# IotaWatt3_2.net
KiCad netlist of a schematic drawn in EAGLE
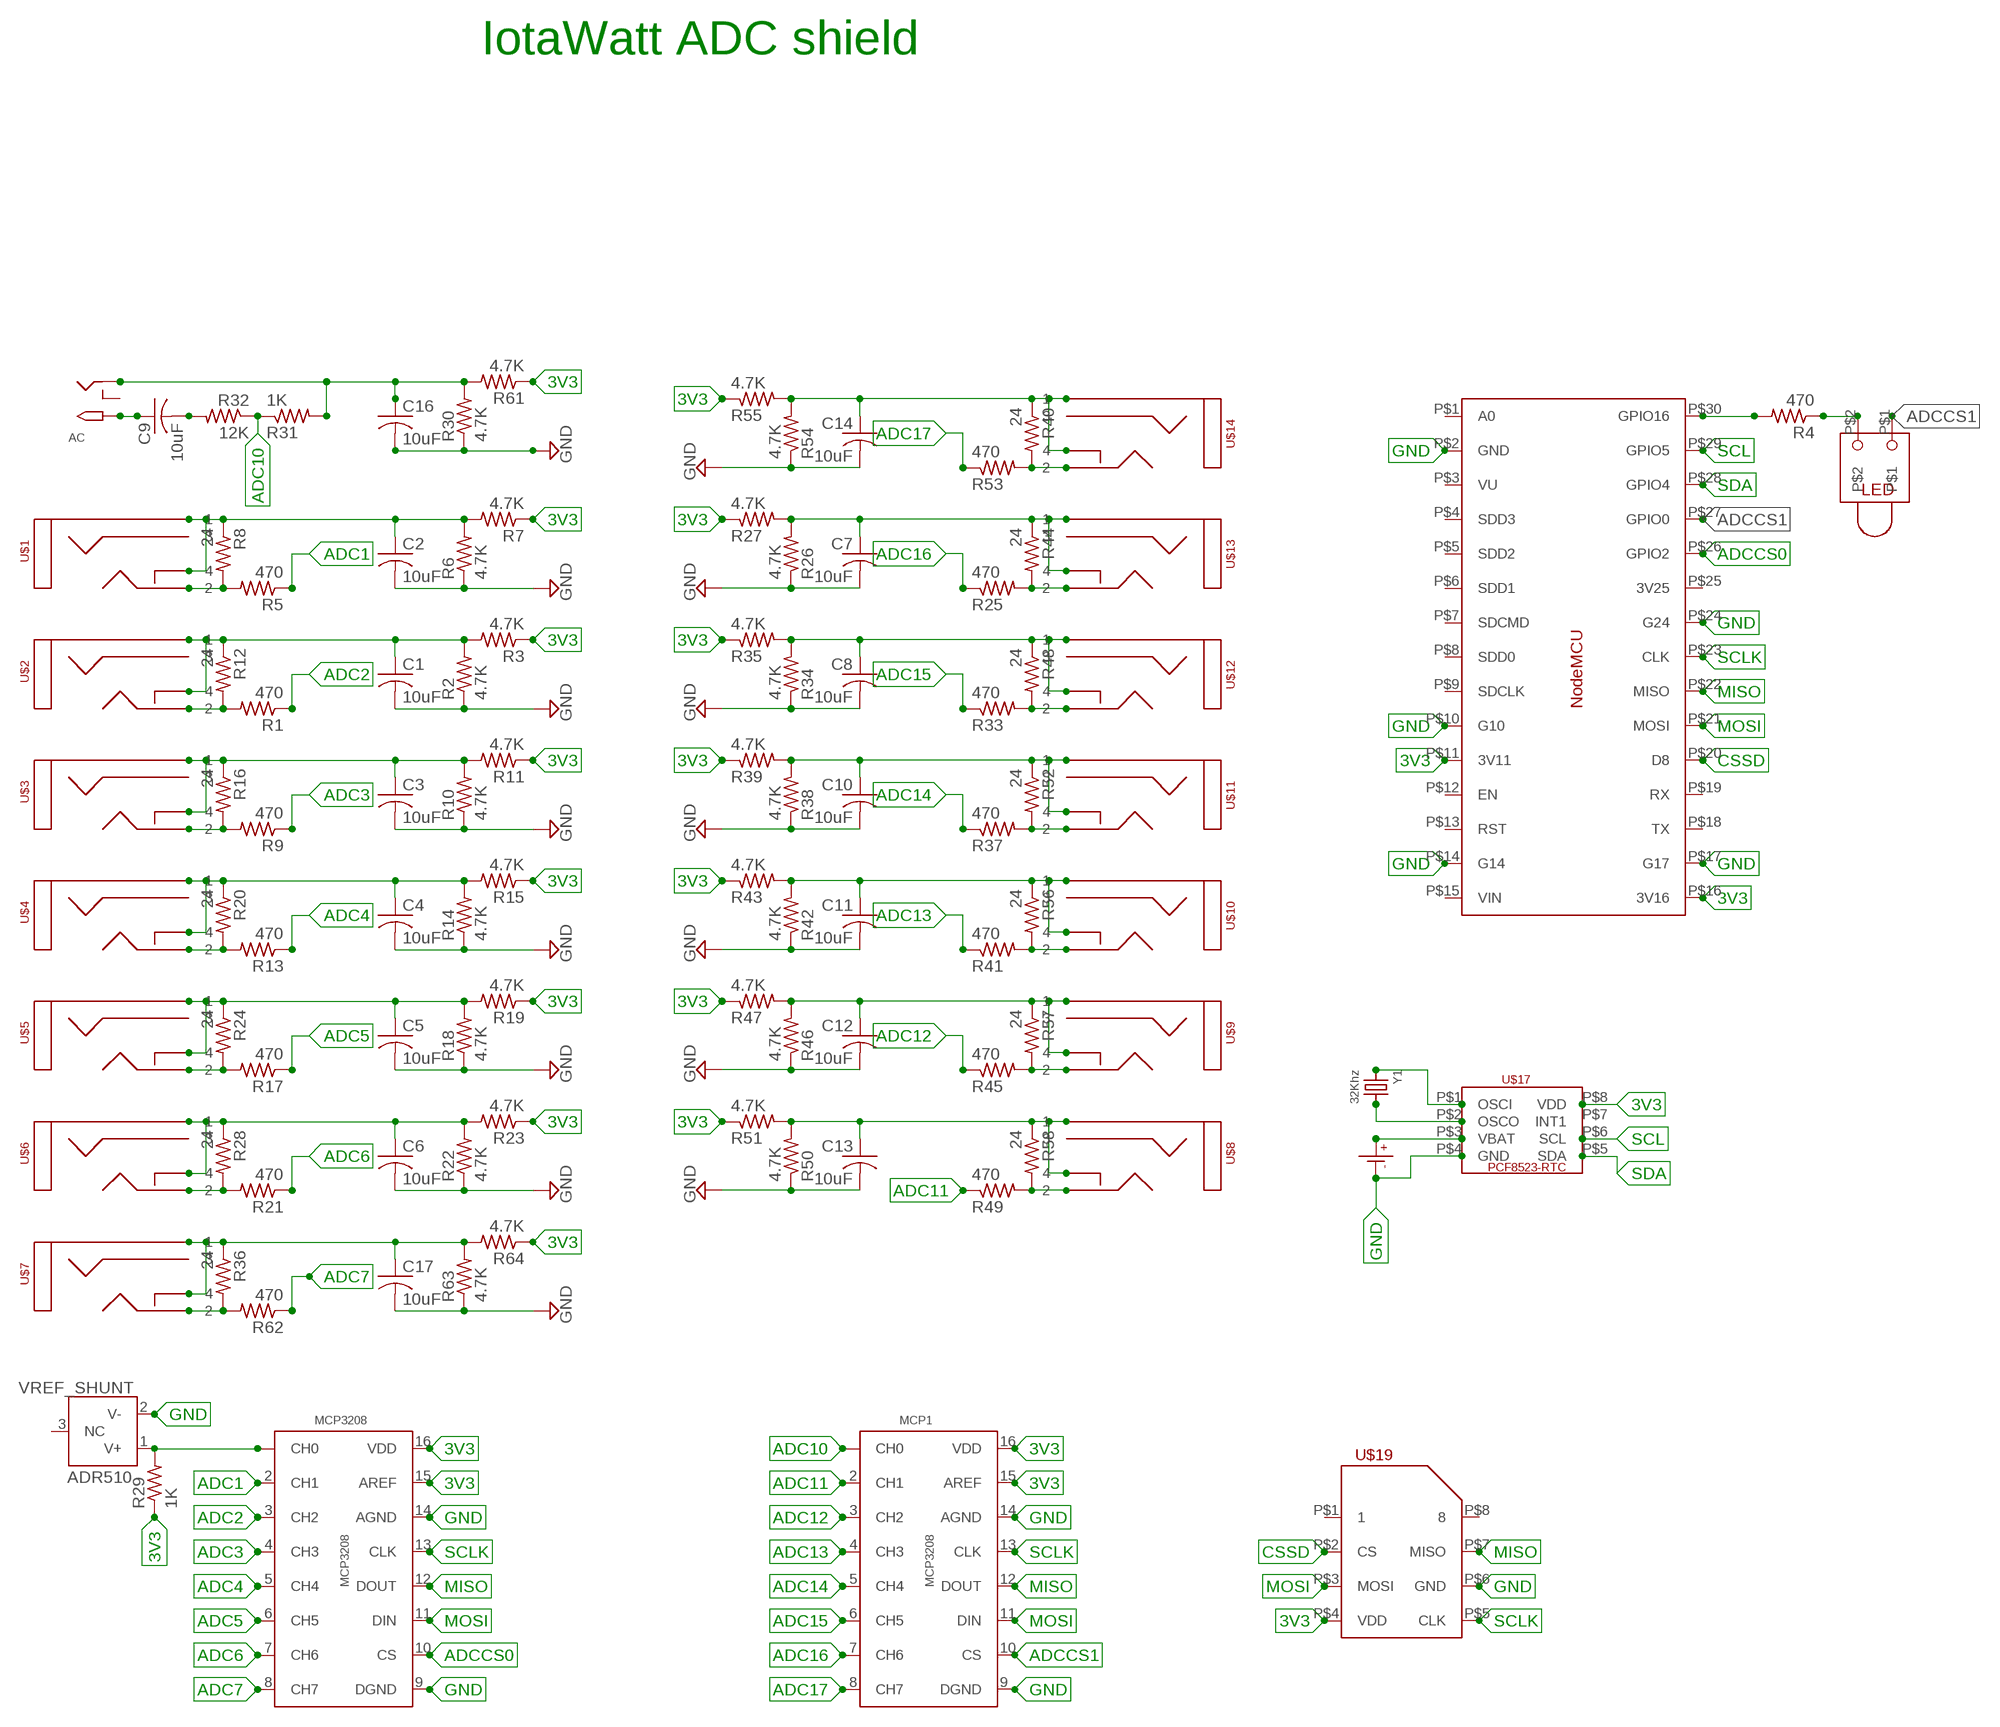
[diagram p0: schematic, sheet 1]

(export (version "E")
  (design (tool "Eeschema 10.0.6"))
  (components
    (comp (ref "AC")
      (value "2.1MMJACKSMT")
      (footprint "eagle-import:DCJACK_2MM_SMT")
      (libsource (lib "eagle-import") (part "2.1MMJACKSMT"))
    )
    (comp (ref "ADR510")
      (value "VREF_SHUNT")
      (footprint "eagle-import:SOT23_3")
      (libsource (lib "eagle-import") (part "VREF_SHUNT"))
    )
    (comp (ref "C1")
      (value "10uF")
      (footprint "eagle-import:C0805")
      (libsource (lib "eagle-import") (part "C-USC0805"))
    )
    (comp (ref "C2")
      (value "10uF")
      (footprint "eagle-import:C0805")
      (libsource (lib "eagle-import") (part "C-USC0805"))
    )
    (comp (ref "C3")
      (value "10uF")
      (footprint "eagle-import:C0805")
      (libsource (lib "eagle-import") (part "C-USC0805"))
    )
    (comp (ref "C4")
      (value "10uF")
      (footprint "eagle-import:C0805")
      (libsource (lib "eagle-import") (part "C-USC0805"))
    )
    (comp (ref "C5")
      (value "10uF")
      (footprint "eagle-import:C0805")
      (libsource (lib "eagle-import") (part "C-USC0805"))
    )
    (comp (ref "C6")
      (value "10uF")
      (footprint "eagle-import:C0805")
      (libsource (lib "eagle-import") (part "C-USC0805"))
    )
    (comp (ref "C7")
      (value "10uF")
      (footprint "eagle-import:C0805")
      (libsource (lib "eagle-import") (part "C-USC0805"))
    )
    (comp (ref "C8")
      (value "10uF")
      (footprint "eagle-import:C0805")
      (libsource (lib "eagle-import") (part "C-USC0805"))
    )
    (comp (ref "C9")
      (value "10uF")
      (footprint "eagle-import:C0805")
      (libsource (lib "eagle-import") (part "C-USC0805"))
    )
    (comp (ref "C10")
      (value "10uF")
      (footprint "eagle-import:C0805")
      (libsource (lib "eagle-import") (part "C-USC0805"))
    )
    (comp (ref "C11")
      (value "10uF")
      (footprint "eagle-import:C0805")
      (libsource (lib "eagle-import") (part "C-USC0805"))
    )
    (comp (ref "C12")
      (value "10uF")
      (footprint "eagle-import:C0805")
      (libsource (lib "eagle-import") (part "C-USC0805"))
    )
    (comp (ref "C13")
      (value "10uF")
      (footprint "eagle-import:C0805")
      (libsource (lib "eagle-import") (part "C-USC0805"))
    )
    (comp (ref "C14")
      (value "10uF")
      (footprint "eagle-import:C0805")
      (libsource (lib "eagle-import") (part "C-USC0805"))
    )
    (comp (ref "C16")
      (value "10uF")
      (footprint "eagle-import:C0805")
      (libsource (lib "eagle-import") (part "C-USC0805"))
    )
    (comp (ref "C17")
      (value "10uF")
      (footprint "eagle-import:C0805")
      (libsource (lib "eagle-import") (part "C-USC0805"))
    )
    (comp (ref "MCP1")
      (value "MCP3208")
      (footprint "eagle-import:SOIC_16")
      (libsource (lib "eagle-import") (part "MCP3208"))
    )
    (comp (ref "MCP3208")
      (value "MCP3208")
      (footprint "eagle-import:SOIC_16")
      (libsource (lib "eagle-import") (part "MCP3208"))
    )
    (comp (ref "R1")
      (value "470")
      (footprint "eagle-import:R0805")
      (libsource (lib "eagle-import") (part "R-US_R0805"))
    )
    (comp (ref "R2")
      (value "4.7K")
      (footprint "eagle-import:R0805")
      (libsource (lib "eagle-import") (part "R-US_R0805"))
    )
    (comp (ref "R3")
      (value "4.7K")
      (footprint "eagle-import:R0805")
      (libsource (lib "eagle-import") (part "R-US_R0805"))
    )
    (comp (ref "R4")
      (value "470")
      (footprint "eagle-import:R0805")
      (libsource (lib "eagle-import") (part "R-US_R0805"))
    )
    (comp (ref "R5")
      (value "470")
      (footprint "eagle-import:R0805")
      (libsource (lib "eagle-import") (part "R-US_R0805"))
    )
    (comp (ref "R6")
      (value "4.7K")
      (footprint "eagle-import:R0805")
      (libsource (lib "eagle-import") (part "R-US_R0805"))
    )
    (comp (ref "R7")
      (value "4.7K")
      (footprint "eagle-import:R0805")
      (libsource (lib "eagle-import") (part "R-US_R0805"))
    )
    (comp (ref "R8")
      (value "24")
      (footprint "eagle-import:R0805")
      (libsource (lib "eagle-import") (part "R-US_R0805"))
    )
    (comp (ref "R9")
      (value "470")
      (footprint "eagle-import:R0805")
      (libsource (lib "eagle-import") (part "R-US_R0805"))
    )
    (comp (ref "R10")
      (value "4.7K")
      (footprint "eagle-import:R0805")
      (libsource (lib "eagle-import") (part "R-US_R0805"))
    )
    (comp (ref "R11")
      (value "4.7K")
      (footprint "eagle-import:R0805")
      (libsource (lib "eagle-import") (part "R-US_R0805"))
    )
    (comp (ref "R12")
      (value "24")
      (footprint "eagle-import:R0805")
      (libsource (lib "eagle-import") (part "R-US_R0805"))
    )
    (comp (ref "R13")
      (value "470")
      (footprint "eagle-import:R0805")
      (libsource (lib "eagle-import") (part "R-US_R0805"))
    )
    (comp (ref "R14")
      (value "4.7K")
      (footprint "eagle-import:R0805")
      (libsource (lib "eagle-import") (part "R-US_R0805"))
    )
    (comp (ref "R15")
      (value "4.7K")
      (footprint "eagle-import:R0805")
      (libsource (lib "eagle-import") (part "R-US_R0805"))
    )
    (comp (ref "R16")
      (value "24")
      (footprint "eagle-import:R0805")
      (libsource (lib "eagle-import") (part "R-US_R0805"))
    )
    (comp (ref "R17")
      (value "470")
      (footprint "eagle-import:R0805")
      (libsource (lib "eagle-import") (part "R-US_R0805"))
    )
    (comp (ref "R18")
      (value "4.7K")
      (footprint "eagle-import:R0805")
      (libsource (lib "eagle-import") (part "R-US_R0805"))
    )
    (comp (ref "R19")
      (value "4.7K")
      (footprint "eagle-import:R0805")
      (libsource (lib "eagle-import") (part "R-US_R0805"))
    )
    (comp (ref "R20")
      (value "24")
      (footprint "eagle-import:R0805")
      (libsource (lib "eagle-import") (part "R-US_R0805"))
    )
    (comp (ref "R21")
      (value "470")
      (footprint "eagle-import:R0805")
      (libsource (lib "eagle-import") (part "R-US_R0805"))
    )
    (comp (ref "R22")
      (value "4.7K")
      (footprint "eagle-import:R0805")
      (libsource (lib "eagle-import") (part "R-US_R0805"))
    )
    (comp (ref "R23")
      (value "4.7K")
      (footprint "eagle-import:R0805")
      (libsource (lib "eagle-import") (part "R-US_R0805"))
    )
    (comp (ref "R24")
      (value "24")
      (footprint "eagle-import:R0805")
      (libsource (lib "eagle-import") (part "R-US_R0805"))
    )
    (comp (ref "R25")
      (value "470")
      (footprint "eagle-import:R0805")
      (libsource (lib "eagle-import") (part "R-US_R0805"))
    )
    (comp (ref "R26")
      (value "4.7K")
      (footprint "eagle-import:R0805")
      (libsource (lib "eagle-import") (part "R-US_R0805"))
    )
    (comp (ref "R27")
      (value "4.7K")
      (footprint "eagle-import:R0805")
      (libsource (lib "eagle-import") (part "R-US_R0805"))
    )
    (comp (ref "R28")
      (value "24")
      (footprint "eagle-import:R0805")
      (libsource (lib "eagle-import") (part "R-US_R0805"))
    )
    (comp (ref "R29")
      (value "1K")
      (footprint "eagle-import:R0805")
      (libsource (lib "eagle-import") (part "R-US_R0805"))
    )
    (comp (ref "R30")
      (value "4.7K")
      (footprint "eagle-import:R0805")
      (libsource (lib "eagle-import") (part "R-US_R0805"))
    )
    (comp (ref "R31")
      (value "1K")
      (footprint "eagle-import:R0805")
      (libsource (lib "eagle-import") (part "R-US_R0805"))
    )
    (comp (ref "R32")
      (value "12K")
      (footprint "eagle-import:R0805")
      (libsource (lib "eagle-import") (part "R-US_R0805"))
    )
    (comp (ref "R33")
      (value "470")
      (footprint "eagle-import:R0805")
      (libsource (lib "eagle-import") (part "R-US_R0805"))
    )
    (comp (ref "R34")
      (value "4.7K")
      (footprint "eagle-import:R0805")
      (libsource (lib "eagle-import") (part "R-US_R0805"))
    )
    (comp (ref "R35")
      (value "4.7K")
      (footprint "eagle-import:R0805")
      (libsource (lib "eagle-import") (part "R-US_R0805"))
    )
    (comp (ref "R36")
      (value "24")
      (footprint "eagle-import:R0805")
      (libsource (lib "eagle-import") (part "R-US_R0805"))
    )
    (comp (ref "R37")
      (value "470")
      (footprint "eagle-import:R0805")
      (libsource (lib "eagle-import") (part "R-US_R0805"))
    )
    (comp (ref "R38")
      (value "4.7K")
      (footprint "eagle-import:R0805")
      (libsource (lib "eagle-import") (part "R-US_R0805"))
    )
    (comp (ref "R39")
      (value "4.7K")
      (footprint "eagle-import:R0805")
      (libsource (lib "eagle-import") (part "R-US_R0805"))
    )
    (comp (ref "R40")
      (value "24")
      (footprint "eagle-import:R0805")
      (libsource (lib "eagle-import") (part "R-US_R0805"))
    )
    (comp (ref "R41")
      (value "470")
      (footprint "eagle-import:R0805")
      (libsource (lib "eagle-import") (part "R-US_R0805"))
    )
    (comp (ref "R42")
      (value "4.7K")
      (footprint "eagle-import:R0805")
      (libsource (lib "eagle-import") (part "R-US_R0805"))
    )
    (comp (ref "R43")
      (value "4.7K")
      (footprint "eagle-import:R0805")
      (libsource (lib "eagle-import") (part "R-US_R0805"))
    )
    (comp (ref "R44")
      (value "24")
      (footprint "eagle-import:R0805")
      (libsource (lib "eagle-import") (part "R-US_R0805"))
    )
    (comp (ref "R45")
      (value "470")
      (footprint "eagle-import:R0805")
      (libsource (lib "eagle-import") (part "R-US_R0805"))
    )
    (comp (ref "R46")
      (value "4.7K")
      (footprint "eagle-import:R0805")
      (libsource (lib "eagle-import") (part "R-US_R0805"))
    )
    (comp (ref "R47")
      (value "4.7K")
      (footprint "eagle-import:R0805")
      (libsource (lib "eagle-import") (part "R-US_R0805"))
    )
    (comp (ref "R48")
      (value "24")
      (footprint "eagle-import:R0805")
      (libsource (lib "eagle-import") (part "R-US_R0805"))
    )
    (comp (ref "R49")
      (value "470")
      (footprint "eagle-import:R0805")
      (libsource (lib "eagle-import") (part "R-US_R0805"))
    )
    (comp (ref "R50")
      (value "4.7K")
      (footprint "eagle-import:R0805")
      (libsource (lib "eagle-import") (part "R-US_R0805"))
    )
    (comp (ref "R51")
      (value "4.7K")
      (footprint "eagle-import:R0805")
      (libsource (lib "eagle-import") (part "R-US_R0805"))
    )
    (comp (ref "R52")
      (value "24")
      (footprint "eagle-import:R0805")
      (libsource (lib "eagle-import") (part "R-US_R0805"))
    )
    (comp (ref "R53")
      (value "470")
      (footprint "eagle-import:R0805")
      (libsource (lib "eagle-import") (part "R-US_R0805"))
    )
    (comp (ref "R54")
      (value "4.7K")
      (footprint "eagle-import:R0805")
      (libsource (lib "eagle-import") (part "R-US_R0805"))
    )
    (comp (ref "R55")
      (value "4.7K")
      (footprint "eagle-import:R0805")
      (libsource (lib "eagle-import") (part "R-US_R0805"))
    )
    (comp (ref "R56")
      (value "24")
      (footprint "eagle-import:R0805")
      (libsource (lib "eagle-import") (part "R-US_R0805"))
    )
    (comp (ref "R57")
      (value "24")
      (footprint "eagle-import:R0805")
      (libsource (lib "eagle-import") (part "R-US_R0805"))
    )
    (comp (ref "R58")
      (value "24")
      (footprint "eagle-import:R0805")
      (libsource (lib "eagle-import") (part "R-US_R0805"))
    )
    (comp (ref "R61")
      (value "4.7K")
      (footprint "eagle-import:R0805")
      (libsource (lib "eagle-import") (part "R-US_R0805"))
    )
    (comp (ref "R62")
      (value "470")
      (footprint "eagle-import:R0805")
      (libsource (lib "eagle-import") (part "R-US_R0805"))
    )
    (comp (ref "R63")
      (value "4.7K")
      (footprint "eagle-import:R0805")
      (libsource (lib "eagle-import") (part "R-US_R0805"))
    )
    (comp (ref "R64")
      (value "4.7K")
      (footprint "eagle-import:R0805")
      (libsource (lib "eagle-import") (part "R-US_R0805"))
    )
    (comp (ref "U$1")
      (value "STEREO_SMD")
      (footprint "eagle-import:STEREO_SMT")
      (libsource (lib "eagle-import") (part "STEREO_SMD"))
    )
    (comp (ref "U$2")
      (value "STEREO_SMD")
      (footprint "eagle-import:STEREO_SMT")
      (libsource (lib "eagle-import") (part "STEREO_SMD"))
    )
    (comp (ref "U$3")
      (value "STEREO_SMD")
      (footprint "eagle-import:STEREO_SMT")
      (libsource (lib "eagle-import") (part "STEREO_SMD"))
    )
    (comp (ref "U$4")
      (value "STEREO_SMD")
      (footprint "eagle-import:STEREO_SMT")
      (libsource (lib "eagle-import") (part "STEREO_SMD"))
    )
    (comp (ref "U$5")
      (value "STEREO_SMD")
      (footprint "eagle-import:STEREO_SMT")
      (libsource (lib "eagle-import") (part "STEREO_SMD"))
    )
    (comp (ref "U$6")
      (value "STEREO_SMD")
      (footprint "eagle-import:STEREO_SMT")
      (libsource (lib "eagle-import") (part "STEREO_SMD"))
    )
    (comp (ref "U$7")
      (value "STEREO_SMD")
      (footprint "eagle-import:STEREO_SMT")
      (libsource (lib "eagle-import") (part "STEREO_SMD"))
    )
    (comp (ref "U$8")
      (value "STEREO_SMD")
      (footprint "eagle-import:STEREO_SMT")
      (libsource (lib "eagle-import") (part "STEREO_SMD"))
    )
    (comp (ref "U$9")
      (value "STEREO_SMD")
      (footprint "eagle-import:STEREO_SMT")
      (libsource (lib "eagle-import") (part "STEREO_SMD"))
    )
    (comp (ref "U$10")
      (value "STEREO_SMD")
      (footprint "eagle-import:STEREO_SMT")
      (libsource (lib "eagle-import") (part "STEREO_SMD"))
    )
    (comp (ref "U$11")
      (value "STEREO_SMD")
      (footprint "eagle-import:STEREO_SMT")
      (libsource (lib "eagle-import") (part "STEREO_SMD"))
    )
    (comp (ref "U$12")
      (value "STEREO_SMD")
      (footprint "eagle-import:STEREO_SMT")
      (libsource (lib "eagle-import") (part "STEREO_SMD"))
    )
    (comp (ref "U$13")
      (value "STEREO_SMD")
      (footprint "eagle-import:STEREO_SMT")
      (libsource (lib "eagle-import") (part "STEREO_SMD"))
    )
    (comp (ref "U$14")
      (value "STEREO_SMD")
      (footprint "eagle-import:STEREO_SMT")
      (libsource (lib "eagle-import") (part "STEREO_SMD"))
    )
    (comp (ref "U$15")
      (value "LED_RT_TRH")
      (footprint "eagle-import:LED_TH_RT")
      (libsource (lib "eagle-import") (part "LED_RT_TRH"))
    )
    (comp (ref "U$16")
      (value "NODEMCU")
      (footprint "eagle-import:NODEMCU")
      (libsource (lib "eagle-import") (part "NODEMCU"))
    )
    (comp (ref "U$17")
      (value "PCF8523_RTC")
      (footprint "eagle-import:SOIC_8")
      (libsource (lib "eagle-import") (part "PCF8523_RTC"))
    )
    (comp (ref "U$18")
      (value "CR1220SMD")
      (footprint "eagle-import:CR1220SMD")
      (libsource (lib "eagle-import") (part "CR1220SMD"))
    )
    (comp (ref "U$19")
      (value "MICROSD_PUSH/PULL")
      (footprint "eagle-import:MICROSD")
      (libsource (lib "eagle-import") (part "MICROSD_PUSH/PULL"))
    )
    (comp (ref "Y1")
      (value "32Khz")
      (footprint "eagle-import:CRYSTAL_8X3.8")
      (libsource (lib "eagle-import") (part "CRYSTAL8X3.8SMT"))
    )
  )
  (nets
    (net (code "1") (name "3V3") (class "Default")
      (node (ref "MCP1") (pin "15") (pinfunction "AREF_15") (pintype "input"))
      (node (ref "MCP1") (pin "16") (pinfunction "VDD_16") (pintype "bidirectional"))
      (node (ref "MCP3208") (pin "15") (pinfunction "AREF_15") (pintype "input"))
      (node (ref "MCP3208") (pin "16") (pinfunction "VDD_16") (pintype "bidirectional"))
      (node (ref "R11") (pin "1") (pinfunction "1_1") (pintype "passive"))
      (node (ref "R15") (pin "1") (pinfunction "1_1") (pintype "passive"))
      (node (ref "R19") (pin "1") (pinfunction "1_1") (pintype "passive"))
      (node (ref "R23") (pin "1") (pinfunction "1_1") (pintype "passive"))
      (node (ref "R27") (pin "1") (pinfunction "1_1") (pintype "passive"))
      (node (ref "R29") (pin "1") (pinfunction "1_1") (pintype "passive"))
      (node (ref "R3") (pin "1") (pinfunction "1_1") (pintype "passive"))
      (node (ref "R35") (pin "1") (pinfunction "1_1") (pintype "passive"))
      (node (ref "R39") (pin "1") (pinfunction "1_1") (pintype "passive"))
      (node (ref "R43") (pin "1") (pinfunction "1_1") (pintype "passive"))
      (node (ref "R47") (pin "1") (pinfunction "1_1") (pintype "passive"))
      (node (ref "R51") (pin "1") (pinfunction "1_1") (pintype "passive"))
      (node (ref "R55") (pin "1") (pinfunction "1_1") (pintype "passive"))
      (node (ref "R61") (pin "1") (pinfunction "1_1") (pintype "passive"))
      (node (ref "R64") (pin "1") (pinfunction "1_1") (pintype "passive"))
      (node (ref "R7") (pin "1") (pinfunction "1_1") (pintype "passive"))
      (node (ref "U$16") (pin "P$11") (pinfunction "3V11_P$11") (pintype "bidirectional"))
      (node (ref "U$16") (pin "P$16") (pinfunction "3V16_P$16") (pintype "bidirectional"))
      (node (ref "U$17") (pin "P$8") (pinfunction "VDD_P$8") (pintype "bidirectional"))
      (node (ref "U$19") (pin "P$4") (pinfunction "VDD_P$4") (pintype "bidirectional"))
    )
    (net (code "2") (name "ADC1") (class "Default")
      (node (ref "MCP3208") (pin "2") (pinfunction "CH1_2") (pintype "input"))
      (node (ref "R5") (pin "1") (pinfunction "1_1") (pintype "passive"))
    )
    (net (code "3") (name "ADC2") (class "Default")
      (node (ref "MCP3208") (pin "3") (pinfunction "CH2_3") (pintype "input"))
      (node (ref "R1") (pin "1") (pinfunction "1_1") (pintype "passive"))
    )
    (net (code "4") (name "ADC3") (class "Default")
      (node (ref "MCP3208") (pin "4") (pinfunction "CH3_4") (pintype "input"))
      (node (ref "R9") (pin "1") (pinfunction "1_1") (pintype "passive"))
    )
    (net (code "5") (name "ADC4") (class "Default")
      (node (ref "MCP3208") (pin "5") (pinfunction "CH4_5") (pintype "bidirectional"))
      (node (ref "R13") (pin "1") (pinfunction "1_1") (pintype "passive"))
    )
    (net (code "6") (name "ADC5") (class "Default")
      (node (ref "MCP3208") (pin "6") (pinfunction "CH5_6") (pintype "bidirectional"))
      (node (ref "R17") (pin "1") (pinfunction "1_1") (pintype "passive"))
    )
    (net (code "7") (name "ADC6") (class "Default")
      (node (ref "MCP3208") (pin "7") (pinfunction "CH6_7") (pintype "input"))
      (node (ref "R21") (pin "1") (pinfunction "1_1") (pintype "passive"))
    )
    (net (code "8") (name "ADC7") (class "Default")
      (node (ref "MCP3208") (pin "8") (pinfunction "CH7_8") (pintype "bidirectional"))
      (node (ref "R62") (pin "1") (pinfunction "1_1") (pintype "passive"))
    )
    (net (code "9") (name "ADC10") (class "Default")
      (node (ref "MCP1") (pin "1") (pinfunction "CH0_1") (pintype "input"))
      (node (ref "R31") (pin "1") (pinfunction "1_1") (pintype "passive"))
      (node (ref "R32") (pin "1") (pinfunction "1_1") (pintype "passive"))
    )
    (net (code "10") (name "ADC11") (class "Default")
      (node (ref "MCP1") (pin "2") (pinfunction "CH1_2") (pintype "input"))
      (node (ref "R49") (pin "1") (pinfunction "1_1") (pintype "passive"))
    )
    (net (code "11") (name "ADC12") (class "Default")
      (node (ref "MCP1") (pin "3") (pinfunction "CH2_3") (pintype "input"))
      (node (ref "R45") (pin "1") (pinfunction "1_1") (pintype "passive"))
    )
    (net (code "12") (name "ADC13") (class "Default")
      (node (ref "MCP1") (pin "4") (pinfunction "CH3_4") (pintype "input"))
      (node (ref "R41") (pin "1") (pinfunction "1_1") (pintype "passive"))
    )
    (net (code "13") (name "ADC14") (class "Default")
      (node (ref "MCP1") (pin "5") (pinfunction "CH4_5") (pintype "bidirectional"))
      (node (ref "R37") (pin "1") (pinfunction "1_1") (pintype "passive"))
    )
    (net (code "14") (name "ADC15") (class "Default")
      (node (ref "MCP1") (pin "6") (pinfunction "CH5_6") (pintype "bidirectional"))
      (node (ref "R33") (pin "1") (pinfunction "1_1") (pintype "passive"))
    )
    (net (code "15") (name "ADC16") (class "Default")
      (node (ref "MCP1") (pin "7") (pinfunction "CH6_7") (pintype "input"))
      (node (ref "R25") (pin "1") (pinfunction "1_1") (pintype "passive"))
    )
    (net (code "16") (name "ADC17") (class "Default")
      (node (ref "MCP1") (pin "8") (pinfunction "CH7_8") (pintype "bidirectional"))
      (node (ref "R53") (pin "1") (pinfunction "1_1") (pintype "passive"))
    )
    (net (code "17") (name "ADCCS0") (class "Default")
      (node (ref "MCP3208") (pin "10") (pinfunction "CS_10") (pintype "input"))
      (node (ref "U$16") (pin "P$26") (pinfunction "GPIO2_P$26") (pintype "bidirectional"))
    )
    (net (code "18") (name "ADCCS1") (class "Default")
      (node (ref "MCP1") (pin "10") (pinfunction "CS_10") (pintype "input"))
      (node (ref "U$15") (pin "P$1") (pinfunction "P$1_P$1") (pintype "bidirectional"))
      (node (ref "U$16") (pin "P$27") (pinfunction "GPIO0_P$27") (pintype "bidirectional"))
    )
    (net (code "19") (name "CSSD") (class "Default")
      (node (ref "U$16") (pin "P$20") (pinfunction "D8_P$20") (pintype "bidirectional"))
      (node (ref "U$19") (pin "P$2") (pinfunction "CS_P$2") (pintype "bidirectional"))
    )
    (net (code "20") (name "GND") (class "Default")
      (node (ref "ADR510") (pin "2") (pinfunction "V-_2") (pintype "bidirectional"))
      (node (ref "C1") (pin "2") (pinfunction "2_2") (pintype "passive"))
      (node (ref "C10") (pin "2") (pinfunction "2_2") (pintype "passive"))
      (node (ref "C11") (pin "2") (pinfunction "2_2") (pintype "passive"))
      (node (ref "C12") (pin "2") (pinfunction "2_2") (pintype "passive"))
      (node (ref "C13") (pin "2") (pinfunction "2_2") (pintype "passive"))
      (node (ref "C14") (pin "2") (pinfunction "2_2") (pintype "passive"))
      (node (ref "C16") (pin "2") (pinfunction "2_2") (pintype "passive"))
      (node (ref "C17") (pin "2") (pinfunction "2_2") (pintype "passive"))
      (node (ref "C2") (pin "2") (pinfunction "2_2") (pintype "passive"))
      (node (ref "C3") (pin "2") (pinfunction "2_2") (pintype "passive"))
      (node (ref "C4") (pin "2") (pinfunction "2_2") (pintype "passive"))
      (node (ref "C5") (pin "2") (pinfunction "2_2") (pintype "passive"))
      (node (ref "C6") (pin "2") (pinfunction "2_2") (pintype "passive"))
      (node (ref "C7") (pin "2") (pinfunction "2_2") (pintype "passive"))
      (node (ref "C8") (pin "2") (pinfunction "2_2") (pintype "passive"))
      (node (ref "MCP1") (pin "14") (pinfunction "AGND_14") (pintype "input"))
      (node (ref "MCP1") (pin "9") (pinfunction "DGND_9") (pintype "bidirectional"))
      (node (ref "MCP3208") (pin "14") (pinfunction "AGND_14") (pintype "input"))
      (node (ref "MCP3208") (pin "9") (pinfunction "DGND_9") (pintype "bidirectional"))
      (node (ref "R10") (pin "1") (pinfunction "1_1") (pintype "passive"))
      (node (ref "R14") (pin "1") (pinfunction "1_1") (pintype "passive"))
      (node (ref "R18") (pin "1") (pinfunction "1_1") (pintype "passive"))
      (node (ref "R2") (pin "1") (pinfunction "1_1") (pintype "passive"))
      (node (ref "R22") (pin "1") (pinfunction "1_1") (pintype "passive"))
      (node (ref "R26") (pin "1") (pinfunction "1_1") (pintype "passive"))
      (node (ref "R30") (pin "1") (pinfunction "1_1") (pintype "passive"))
      (node (ref "R34") (pin "1") (pinfunction "1_1") (pintype "passive"))
      (node (ref "R38") (pin "1") (pinfunction "1_1") (pintype "passive"))
      (node (ref "R42") (pin "1") (pinfunction "1_1") (pintype "passive"))
      (node (ref "R46") (pin "1") (pinfunction "1_1") (pintype "passive"))
      (node (ref "R50") (pin "1") (pinfunction "1_1") (pintype "passive"))
      (node (ref "R54") (pin "1") (pinfunction "1_1") (pintype "passive"))
      (node (ref "R6") (pin "1") (pinfunction "1_1") (pintype "passive"))
      (node (ref "R63") (pin "1") (pinfunction "1_1") (pintype "passive"))
      (node (ref "U$16") (pin "P$10") (pinfunction "G10_P$10") (pintype "bidirectional"))
      (node (ref "U$16") (pin "P$14") (pinfunction "G14_P$14") (pintype "bidirectional"))
      (node (ref "U$16") (pin "P$17") (pinfunction "G17_P$17") (pintype "bidirectional"))
      (node (ref "U$16") (pin "P$2") (pinfunction "GND_P$2") (pintype "bidirectional"))
      (node (ref "U$16") (pin "P$24") (pinfunction "G24_P$24") (pintype "bidirectional"))
      (node (ref "U$17") (pin "P$4") (pinfunction "GND_P$4") (pintype "bidirectional"))
      (node (ref "U$18") (pin "P-") (pinfunction "P$-_P-") (pintype "bidirectional"))
      (node (ref "U$19") (pin "P$6") (pinfunction "GND_P$6") (pintype "bidirectional"))
    )
    (net (code "21") (name "MISO") (class "Default")
      (node (ref "MCP1") (pin "12") (pinfunction "DOUT_12") (pintype "bidirectional"))
      (node (ref "MCP3208") (pin "12") (pinfunction "DOUT_12") (pintype "bidirectional"))
      (node (ref "U$16") (pin "P$22") (pinfunction "MISO_P$22") (pintype "bidirectional"))
      (node (ref "U$19") (pin "P$7") (pinfunction "MISO_P$7") (pintype "bidirectional"))
    )
    (net (code "22") (name "MOSI") (class "Default")
      (node (ref "MCP1") (pin "11") (pinfunction "DIN_11") (pintype "input"))
      (node (ref "MCP3208") (pin "11") (pinfunction "DIN_11") (pintype "input"))
      (node (ref "U$16") (pin "P$21") (pinfunction "MOSI_P$21") (pintype "bidirectional"))
      (node (ref "U$19") (pin "P$3") (pinfunction "MOSI_P$3") (pintype "bidirectional"))
    )
    (net (code "23") (name "Net-(AC-RING)") (class "Default")
      (node (ref "AC") (pin "GND") (pinfunction "RING_GND") (pintype "bidirectional"))
      (node (ref "C16") (pin "1") (pinfunction "1_1") (pintype "passive"))
      (node (ref "R30") (pin "2") (pinfunction "2_2") (pintype "passive"))
      (node (ref "R31") (pin "2") (pinfunction "2_2") (pintype "passive"))
      (node (ref "R61") (pin "2") (pinfunction "2_2") (pintype "passive"))
    )
    (net (code "24") (name "Net-(AC-TIP)") (class "Default")
      (node (ref "AC") (pin "PWR2") (pinfunction "TIP_PWR2") (pintype "bidirectional"))
      (node (ref "C9") (pin "1") (pinfunction "1_1") (pintype "passive"))
    )
    (net (code "25") (name "Net-(ADR510-V+)") (class "Default")
      (node (ref "ADR510") (pin "1") (pinfunction "V+_1") (pintype "bidirectional"))
      (node (ref "MCP3208") (pin "1") (pinfunction "CH0_1") (pintype "input"))
      (node (ref "R29") (pin "2") (pinfunction "2_2") (pintype "passive"))
    )
    (net (code "26") (name "Net-(C9-Pad2)") (class "Default")
      (node (ref "C9") (pin "2") (pinfunction "2_2") (pintype "passive"))
      (node (ref "R32") (pin "2") (pinfunction "2_2") (pintype "passive"))
    )
    (net (code "27") (name "Net-(R4-Pad1)") (class "Default")
      (node (ref "R4") (pin "1") (pinfunction "1_1") (pintype "passive"))
      (node (ref "U$15") (pin "P$2") (pinfunction "P$2_P$2") (pintype "bidirectional"))
    )
    (net (code "28") (name "Net-(U$1-1)") (class "Default")
      (node (ref "C2") (pin "1") (pinfunction "1_1") (pintype "passive"))
      (node (ref "R6") (pin "2") (pinfunction "2_2") (pintype "passive"))
      (node (ref "R7") (pin "2") (pinfunction "2_2") (pintype "passive"))
      (node (ref "R8") (pin "1") (pinfunction "1_1") (pintype "passive"))
      (node (ref "U$1") (pin "P$1") (pinfunction "1_P$1") (pintype "bidirectional"))
      (node (ref "U$1") (pin "P$4") (pinfunction "4_P$4") (pintype "bidirectional"))
    )
    (net (code "29") (name "Net-(U$1-2)") (class "Default")
      (node (ref "R5") (pin "2") (pinfunction "2_2") (pintype "passive"))
      (node (ref "R8") (pin "2") (pinfunction "2_2") (pintype "passive"))
      (node (ref "U$1") (pin "P$2") (pinfunction "2_P$2") (pintype "bidirectional"))
    )
    (net (code "30") (name "Net-(U$2-1)") (class "Default")
      (node (ref "C1") (pin "1") (pinfunction "1_1") (pintype "passive"))
      (node (ref "R12") (pin "1") (pinfunction "1_1") (pintype "passive"))
      (node (ref "R2") (pin "2") (pinfunction "2_2") (pintype "passive"))
      (node (ref "R3") (pin "2") (pinfunction "2_2") (pintype "passive"))
      (node (ref "U$2") (pin "P$1") (pinfunction "1_P$1") (pintype "bidirectional"))
      (node (ref "U$2") (pin "P$4") (pinfunction "4_P$4") (pintype "bidirectional"))
    )
    (net (code "31") (name "Net-(U$2-2)") (class "Default")
      (node (ref "R1") (pin "2") (pinfunction "2_2") (pintype "passive"))
      (node (ref "R12") (pin "2") (pinfunction "2_2") (pintype "passive"))
      (node (ref "U$2") (pin "P$2") (pinfunction "2_P$2") (pintype "bidirectional"))
    )
    (net (code "32") (name "Net-(U$3-1)") (class "Default")
      (node (ref "C3") (pin "1") (pinfunction "1_1") (pintype "passive"))
      (node (ref "R10") (pin "2") (pinfunction "2_2") (pintype "passive"))
      (node (ref "R11") (pin "2") (pinfunction "2_2") (pintype "passive"))
      (node (ref "R16") (pin "1") (pinfunction "1_1") (pintype "passive"))
      (node (ref "U$3") (pin "P$1") (pinfunction "1_P$1") (pintype "bidirectional"))
      (node (ref "U$3") (pin "P$4") (pinfunction "4_P$4") (pintype "bidirectional"))
    )
    (net (code "33") (name "Net-(U$3-2)") (class "Default")
      (node (ref "R16") (pin "2") (pinfunction "2_2") (pintype "passive"))
      (node (ref "R9") (pin "2") (pinfunction "2_2") (pintype "passive"))
      (node (ref "U$3") (pin "P$2") (pinfunction "2_P$2") (pintype "bidirectional"))
    )
    (net (code "34") (name "Net-(U$4-1)") (class "Default")
      (node (ref "C4") (pin "1") (pinfunction "1_1") (pintype "passive"))
      (node (ref "R14") (pin "2") (pinfunction "2_2") (pintype "passive"))
      (node (ref "R15") (pin "2") (pinfunction "2_2") (pintype "passive"))
      (node (ref "R20") (pin "1") (pinfunction "1_1") (pintype "passive"))
      (node (ref "U$4") (pin "P$1") (pinfunction "1_P$1") (pintype "bidirectional"))
      (node (ref "U$4") (pin "P$4") (pinfunction "4_P$4") (pintype "bidirectional"))
    )
    (net (code "35") (name "Net-(U$4-2)") (class "Default")
      (node (ref "R13") (pin "2") (pinfunction "2_2") (pintype "passive"))
      (node (ref "R20") (pin "2") (pinfunction "2_2") (pintype "passive"))
      (node (ref "U$4") (pin "P$2") (pinfunction "2_P$2") (pintype "bidirectional"))
    )
    (net (code "36") (name "Net-(U$5-1)") (class "Default")
      (node (ref "C5") (pin "1") (pinfunction "1_1") (pintype "passive"))
      (node (ref "R18") (pin "2") (pinfunction "2_2") (pintype "passive"))
      (node (ref "R19") (pin "2") (pinfunction "2_2") (pintype "passive"))
      (node (ref "R24") (pin "1") (pinfunction "1_1") (pintype "passive"))
      (node (ref "U$5") (pin "P$1") (pinfunction "1_P$1") (pintype "bidirectional"))
      (node (ref "U$5") (pin "P$4") (pinfunction "4_P$4") (pintype "bidirectional"))
    )
    (net (code "37") (name "Net-(U$5-2)") (class "Default")
      (node (ref "R17") (pin "2") (pinfunction "2_2") (pintype "passive"))
      (node (ref "R24") (pin "2") (pinfunction "2_2") (pintype "passive"))
      (node (ref "U$5") (pin "P$2") (pinfunction "2_P$2") (pintype "bidirectional"))
    )
    (net (code "38") (name "Net-(U$6-1)") (class "Default")
      (node (ref "C6") (pin "1") (pinfunction "1_1") (pintype "passive"))
      (node (ref "R22") (pin "2") (pinfunction "2_2") (pintype "passive"))
      (node (ref "R23") (pin "2") (pinfunction "2_2") (pintype "passive"))
      (node (ref "R28") (pin "1") (pinfunction "1_1") (pintype "passive"))
      (node (ref "U$6") (pin "P$1") (pinfunction "1_P$1") (pintype "bidirectional"))
      (node (ref "U$6") (pin "P$4") (pinfunction "4_P$4") (pintype "bidirectional"))
    )
    (net (code "39") (name "Net-(U$6-2)") (class "Default")
      (node (ref "R21") (pin "2") (pinfunction "2_2") (pintype "passive"))
      (node (ref "R28") (pin "2") (pinfunction "2_2") (pintype "passive"))
      (node (ref "U$6") (pin "P$2") (pinfunction "2_P$2") (pintype "bidirectional"))
    )
    (net (code "40") (name "Net-(U$7-1)") (class "Default")
      (node (ref "C17") (pin "1") (pinfunction "1_1") (pintype "passive"))
      (node (ref "R36") (pin "1") (pinfunction "1_1") (pintype "passive"))
      (node (ref "R63") (pin "2") (pinfunction "2_2") (pintype "passive"))
      (node (ref "R64") (pin "2") (pinfunction "2_2") (pintype "passive"))
      (node (ref "U$7") (pin "P$1") (pinfunction "1_P$1") (pintype "bidirectional"))
      (node (ref "U$7") (pin "P$4") (pinfunction "4_P$4") (pintype "bidirectional"))
    )
    (net (code "41") (name "Net-(U$7-2)") (class "Default")
      (node (ref "R36") (pin "2") (pinfunction "2_2") (pintype "passive"))
      (node (ref "R62") (pin "2") (pinfunction "2_2") (pintype "passive"))
      (node (ref "U$7") (pin "P$2") (pinfunction "2_P$2") (pintype "bidirectional"))
    )
    (net (code "42") (name "Net-(U$8-1)") (class "Default")
      (node (ref "C13") (pin "1") (pinfunction "1_1") (pintype "passive"))
      (node (ref "R50") (pin "2") (pinfunction "2_2") (pintype "passive"))
      (node (ref "R51") (pin "2") (pinfunction "2_2") (pintype "passive"))
      (node (ref "R58") (pin "1") (pinfunction "1_1") (pintype "passive"))
      (node (ref "U$8") (pin "P$1") (pinfunction "1_P$1") (pintype "bidirectional"))
      (node (ref "U$8") (pin "P$4") (pinfunction "4_P$4") (pintype "bidirectional"))
    )
    (net (code "43") (name "Net-(U$8-2)") (class "Default")
      (node (ref "R49") (pin "2") (pinfunction "2_2") (pintype "passive"))
      (node (ref "R58") (pin "2") (pinfunction "2_2") (pintype "passive"))
      (node (ref "U$8") (pin "P$2") (pinfunction "2_P$2") (pintype "bidirectional"))
    )
    (net (code "44") (name "Net-(U$9-1)") (class "Default")
      (node (ref "C12") (pin "1") (pinfunction "1_1") (pintype "passive"))
      (node (ref "R46") (pin "2") (pinfunction "2_2") (pintype "passive"))
      (node (ref "R47") (pin "2") (pinfunction "2_2") (pintype "passive"))
      (node (ref "R57") (pin "1") (pinfunction "1_1") (pintype "passive"))
      (node (ref "U$9") (pin "P$1") (pinfunction "1_P$1") (pintype "bidirectional"))
      (node (ref "U$9") (pin "P$4") (pinfunction "4_P$4") (pintype "bidirectional"))
    )
    (net (code "45") (name "Net-(U$9-2)") (class "Default")
      (node (ref "R45") (pin "2") (pinfunction "2_2") (pintype "passive"))
      (node (ref "R57") (pin "2") (pinfunction "2_2") (pintype "passive"))
      (node (ref "U$9") (pin "P$2") (pinfunction "2_P$2") (pintype "bidirectional"))
    )
    (net (code "46") (name "Net-(U$10-1)") (class "Default")
      (node (ref "C11") (pin "1") (pinfunction "1_1") (pintype "passive"))
      (node (ref "R42") (pin "2") (pinfunction "2_2") (pintype "passive"))
      (node (ref "R43") (pin "2") (pinfunction "2_2") (pintype "passive"))
      (node (ref "R56") (pin "1") (pinfunction "1_1") (pintype "passive"))
      (node (ref "U$10") (pin "P$1") (pinfunction "1_P$1") (pintype "bidirectional"))
      (node (ref "U$10") (pin "P$4") (pinfunction "4_P$4") (pintype "bidirectional"))
    )
    (net (code "47") (name "Net-(U$10-2)") (class "Default")
      (node (ref "R41") (pin "2") (pinfunction "2_2") (pintype "passive"))
      (node (ref "R56") (pin "2") (pinfunction "2_2") (pintype "passive"))
      (node (ref "U$10") (pin "P$2") (pinfunction "2_P$2") (pintype "bidirectional"))
    )
    (net (code "48") (name "Net-(U$11-1)") (class "Default")
      (node (ref "C10") (pin "1") (pinfunction "1_1") (pintype "passive"))
      (node (ref "R38") (pin "2") (pinfunction "2_2") (pintype "passive"))
      (node (ref "R39") (pin "2") (pinfunction "2_2") (pintype "passive"))
      (node (ref "R52") (pin "1") (pinfunction "1_1") (pintype "passive"))
      (node (ref "U$11") (pin "P$1") (pinfunction "1_P$1") (pintype "bidirectional"))
      (node (ref "U$11") (pin "P$4") (pinfunction "4_P$4") (pintype "bidirectional"))
    )
    (net (code "49") (name "Net-(U$11-2)") (class "Default")
      (node (ref "R37") (pin "2") (pinfunction "2_2") (pintype "passive"))
      (node (ref "R52") (pin "2") (pinfunction "2_2") (pintype "passive"))
      (node (ref "U$11") (pin "P$2") (pinfunction "2_P$2") (pintype "bidirectional"))
    )
    (net (code "50") (name "Net-(U$12-1)") (class "Default")
      (node (ref "C8") (pin "1") (pinfunction "1_1") (pintype "passive"))
      (node (ref "R34") (pin "2") (pinfunction "2_2") (pintype "passive"))
      (node (ref "R35") (pin "2") (pinfunction "2_2") (pintype "passive"))
      (node (ref "R48") (pin "1") (pinfunction "1_1") (pintype "passive"))
      (node (ref "U$12") (pin "P$1") (pinfunction "1_P$1") (pintype "bidirectional"))
      (node (ref "U$12") (pin "P$4") (pinfunction "4_P$4") (pintype "bidirectional"))
    )
    (net (code "51") (name "Net-(U$12-2)") (class "Default")
      (node (ref "R33") (pin "2") (pinfunction "2_2") (pintype "passive"))
      (node (ref "R48") (pin "2") (pinfunction "2_2") (pintype "passive"))
      (node (ref "U$12") (pin "P$2") (pinfunction "2_P$2") (pintype "bidirectional"))
    )
    (net (code "52") (name "Net-(U$13-1)") (class "Default")
      (node (ref "C7") (pin "1") (pinfunction "1_1") (pintype "passive"))
      (node (ref "R26") (pin "2") (pinfunction "2_2") (pintype "passive"))
      (node (ref "R27") (pin "2") (pinfunction "2_2") (pintype "passive"))
      (node (ref "R44") (pin "1") (pinfunction "1_1") (pintype "passive"))
      (node (ref "U$13") (pin "P$1") (pinfunction "1_P$1") (pintype "bidirectional"))
      (node (ref "U$13") (pin "P$4") (pinfunction "4_P$4") (pintype "bidirectional"))
    )
    (net (code "53") (name "Net-(U$13-2)") (class "Default")
      (node (ref "R25") (pin "2") (pinfunction "2_2") (pintype "passive"))
      (node (ref "R44") (pin "2") (pinfunction "2_2") (pintype "passive"))
      (node (ref "U$13") (pin "P$2") (pinfunction "2_P$2") (pintype "bidirectional"))
    )
    (net (code "54") (name "Net-(U$14-1)") (class "Default")
      (node (ref "C14") (pin "1") (pinfunction "1_1") (pintype "passive"))
      (node (ref "R40") (pin "1") (pinfunction "1_1") (pintype "passive"))
      (node (ref "R54") (pin "2") (pinfunction "2_2") (pintype "passive"))
      (node (ref "R55") (pin "2") (pinfunction "2_2") (pintype "passive"))
      (node (ref "U$14") (pin "P$1") (pinfunction "1_P$1") (pintype "bidirectional"))
      (node (ref "U$14") (pin "P$4") (pinfunction "4_P$4") (pintype "bidirectional"))
    )
    (net (code "55") (name "Net-(U$14-2)") (class "Default")
      (node (ref "R40") (pin "2") (pinfunction "2_2") (pintype "passive"))
      (node (ref "R53") (pin "2") (pinfunction "2_2") (pintype "passive"))
      (node (ref "U$14") (pin "P$2") (pinfunction "2_P$2") (pintype "bidirectional"))
    )
    (net (code "56") (name "Net-(U$16-GPIO16)") (class "Default")
      (node (ref "R4") (pin "2") (pinfunction "2_2") (pintype "passive"))
      (node (ref "U$16") (pin "P$30") (pinfunction "GPIO16_P$30") (pintype "bidirectional"))
    )
    (net (code "57") (name "Net-(U$17-OSCI)") (class "Default")
      (node (ref "U$17") (pin "P$1") (pinfunction "OSCI_P$1") (pintype "bidirectional"))
      (node (ref "Y1") (pin "P$1") (pinfunction "1_P$1") (pintype "passive"))
    )
    (net (code "58") (name "Net-(U$17-OSCO)") (class "Default")
      (node (ref "U$17") (pin "P$2") (pinfunction "OSCO_P$2") (pintype "bidirectional"))
      (node (ref "Y1") (pin "P$4") (pinfunction "2_P$4") (pintype "passive"))
    )
    (net (code "59") (name "Net-(U$17-VBAT)") (class "Default")
      (node (ref "U$17") (pin "P$3") (pinfunction "VBAT_P$3") (pintype "bidirectional"))
      (node (ref "U$18") (pin "P+") (pinfunction "P$+_P+") (pintype "bidirectional"))
    )
    (net (code "60") (name "SCL") (class "Default")
      (node (ref "U$16") (pin "P$29") (pinfunction "GPIO5_P$29") (pintype "bidirectional"))
      (node (ref "U$17") (pin "P$6") (pinfunction "SCL_P$6") (pintype "bidirectional"))
    )
    (net (code "61") (name "SCLK") (class "Default")
      (node (ref "MCP1") (pin "13") (pinfunction "CLK_13") (pintype "input"))
      (node (ref "MCP3208") (pin "13") (pinfunction "CLK_13") (pintype "input"))
      (node (ref "U$16") (pin "P$23") (pinfunction "CLK_P$23") (pintype "bidirectional"))
      (node (ref "U$19") (pin "P$5") (pinfunction "CLK_P$5") (pintype "bidirectional"))
    )
    (net (code "62") (name "SDA") (class "Default")
      (node (ref "U$16") (pin "P$28") (pinfunction "GPIO4_P$28") (pintype "bidirectional"))
      (node (ref "U$17") (pin "P$5") (pinfunction "SDA_P$5") (pintype "bidirectional"))
    )
    (net (code "63") (name "unconnected-(AC-RING_SW-PadGNDBREAK)") (class "Default")
      (node (ref "AC") (pin "GNDBREAK") (pinfunction "RING_SW_GNDBREAK") (pintype "bidirectional"))
    )
    (net (code "64") (name "unconnected-(ADR510-NC-Pad3)") (class "Default")
      (node (ref "ADR510") (pin "3") (pinfunction "NC_3") (pintype "bidirectional"))
    )
    (net (code "65") (name "unconnected-(U$1-3-PadP$3)") (class "Default")
      (node (ref "U$1") (pin "P$3") (pinfunction "3_P$3") (pintype "bidirectional"))
    )
    (net (code "66") (name "unconnected-(U$2-3-PadP$3)") (class "Default")
      (node (ref "U$2") (pin "P$3") (pinfunction "3_P$3") (pintype "bidirectional"))
    )
    (net (code "67") (name "unconnected-(U$3-3-PadP$3)") (class "Default")
      (node (ref "U$3") (pin "P$3") (pinfunction "3_P$3") (pintype "bidirectional"))
    )
    (net (code "68") (name "unconnected-(U$4-3-PadP$3)") (class "Default")
      (node (ref "U$4") (pin "P$3") (pinfunction "3_P$3") (pintype "bidirectional"))
    )
    (net (code "69") (name "unconnected-(U$5-3-PadP$3)") (class "Default")
      (node (ref "U$5") (pin "P$3") (pinfunction "3_P$3") (pintype "bidirectional"))
    )
    (net (code "70") (name "unconnected-(U$6-3-PadP$3)") (class "Default")
      (node (ref "U$6") (pin "P$3") (pinfunction "3_P$3") (pintype "bidirectional"))
    )
    (net (code "71") (name "unconnected-(U$7-3-PadP$3)") (class "Default")
      (node (ref "U$7") (pin "P$3") (pinfunction "3_P$3") (pintype "bidirectional"))
    )
    (net (code "72") (name "unconnected-(U$8-3-PadP$3)") (class "Default")
      (node (ref "U$8") (pin "P$3") (pinfunction "3_P$3") (pintype "bidirectional"))
    )
    (net (code "73") (name "unconnected-(U$9-3-PadP$3)") (class "Default")
      (node (ref "U$9") (pin "P$3") (pinfunction "3_P$3") (pintype "bidirectional"))
    )
    (net (code "74") (name "unconnected-(U$10-3-PadP$3)") (class "Default")
      (node (ref "U$10") (pin "P$3") (pinfunction "3_P$3") (pintype "bidirectional"))
    )
    (net (code "75") (name "unconnected-(U$11-3-PadP$3)") (class "Default")
      (node (ref "U$11") (pin "P$3") (pinfunction "3_P$3") (pintype "bidirectional"))
    )
    (net (code "76") (name "unconnected-(U$12-3-PadP$3)") (class "Default")
      (node (ref "U$12") (pin "P$3") (pinfunction "3_P$3") (pintype "bidirectional"))
    )
    (net (code "77") (name "unconnected-(U$13-3-PadP$3)") (class "Default")
      (node (ref "U$13") (pin "P$3") (pinfunction "3_P$3") (pintype "bidirectional"))
    )
    (net (code "78") (name "unconnected-(U$14-3-PadP$3)") (class "Default")
      (node (ref "U$14") (pin "P$3") (pinfunction "3_P$3") (pintype "bidirectional"))
    )
    (net (code "79") (name "unconnected-(U$16-3V25-PadP$25)") (class "Default")
      (node (ref "U$16") (pin "P$25") (pinfunction "3V25_P$25") (pintype "bidirectional"))
    )
    (net (code "80") (name "unconnected-(U$16-A0-PadP$1)") (class "Default")
      (node (ref "U$16") (pin "P$1") (pinfunction "A0_P$1") (pintype "bidirectional"))
    )
    (net (code "81") (name "unconnected-(U$16-EN-PadP$12)") (class "Default")
      (node (ref "U$16") (pin "P$12") (pinfunction "EN_P$12") (pintype "bidirectional"))
    )
    (net (code "82") (name "unconnected-(U$16-RST-PadP$13)") (class "Default")
      (node (ref "U$16") (pin "P$13") (pinfunction "RST_P$13") (pintype "bidirectional"))
    )
    (net (code "83") (name "unconnected-(U$16-RX-PadP$19)") (class "Default")
      (node (ref "U$16") (pin "P$19") (pinfunction "RX_P$19") (pintype "bidirectional"))
    )
    (net (code "84") (name "unconnected-(U$16-SDCLK-PadP$9)") (class "Default")
      (node (ref "U$16") (pin "P$9") (pinfunction "SDCLK_P$9") (pintype "bidirectional"))
    )
    (net (code "85") (name "unconnected-(U$16-SDCMD-PadP$7)") (class "Default")
      (node (ref "U$16") (pin "P$7") (pinfunction "SDCMD_P$7") (pintype "bidirectional"))
    )
    (net (code "86") (name "unconnected-(U$16-SDD0-PadP$8)") (class "Default")
      (node (ref "U$16") (pin "P$8") (pinfunction "SDD0_P$8") (pintype "bidirectional"))
    )
    (net (code "87") (name "unconnected-(U$16-SDD1-PadP$6)") (class "Default")
      (node (ref "U$16") (pin "P$6") (pinfunction "SDD1_P$6") (pintype "bidirectional"))
    )
    (net (code "88") (name "unconnected-(U$16-SDD2-PadP$5)") (class "Default")
      (node (ref "U$16") (pin "P$5") (pinfunction "SDD2_P$5") (pintype "bidirectional"))
    )
    (net (code "89") (name "unconnected-(U$16-SDD3-PadP$4)") (class "Default")
      (node (ref "U$16") (pin "P$4") (pinfunction "SDD3_P$4") (pintype "bidirectional"))
    )
    (net (code "90") (name "unconnected-(U$16-TX-PadP$18)") (class "Default")
      (node (ref "U$16") (pin "P$18") (pinfunction "TX_P$18") (pintype "bidirectional"))
    )
    (net (code "91") (name "unconnected-(U$16-VIN-PadP$15)") (class "Default")
      (node (ref "U$16") (pin "P$15") (pinfunction "VIN_P$15") (pintype "bidirectional"))
    )
    (net (code "92") (name "unconnected-(U$16-VU-PadP$3)") (class "Default")
      (node (ref "U$16") (pin "P$3") (pinfunction "VU_P$3") (pintype "bidirectional"))
    )
    (net (code "93") (name "unconnected-(U$17-INT1-PadP$7)") (class "Default")
      (node (ref "U$17") (pin "P$7") (pinfunction "INT1_P$7") (pintype "bidirectional"))
    )
    (net (code "94") (name "unconnected-(U$19-1-PadP$1)") (class "Default")
      (node (ref "U$19") (pin "P$1") (pinfunction "1_P$1") (pintype "bidirectional"))
    )
    (net (code "95") (name "unconnected-(U$19-8-PadP$8)") (class "Default")
      (node (ref "U$19") (pin "P$8") (pinfunction "8_P$8") (pintype "bidirectional"))
    )
  )
)
